# alan.net
KiCad netlist of a schematic drawn in EasyEDA Pro
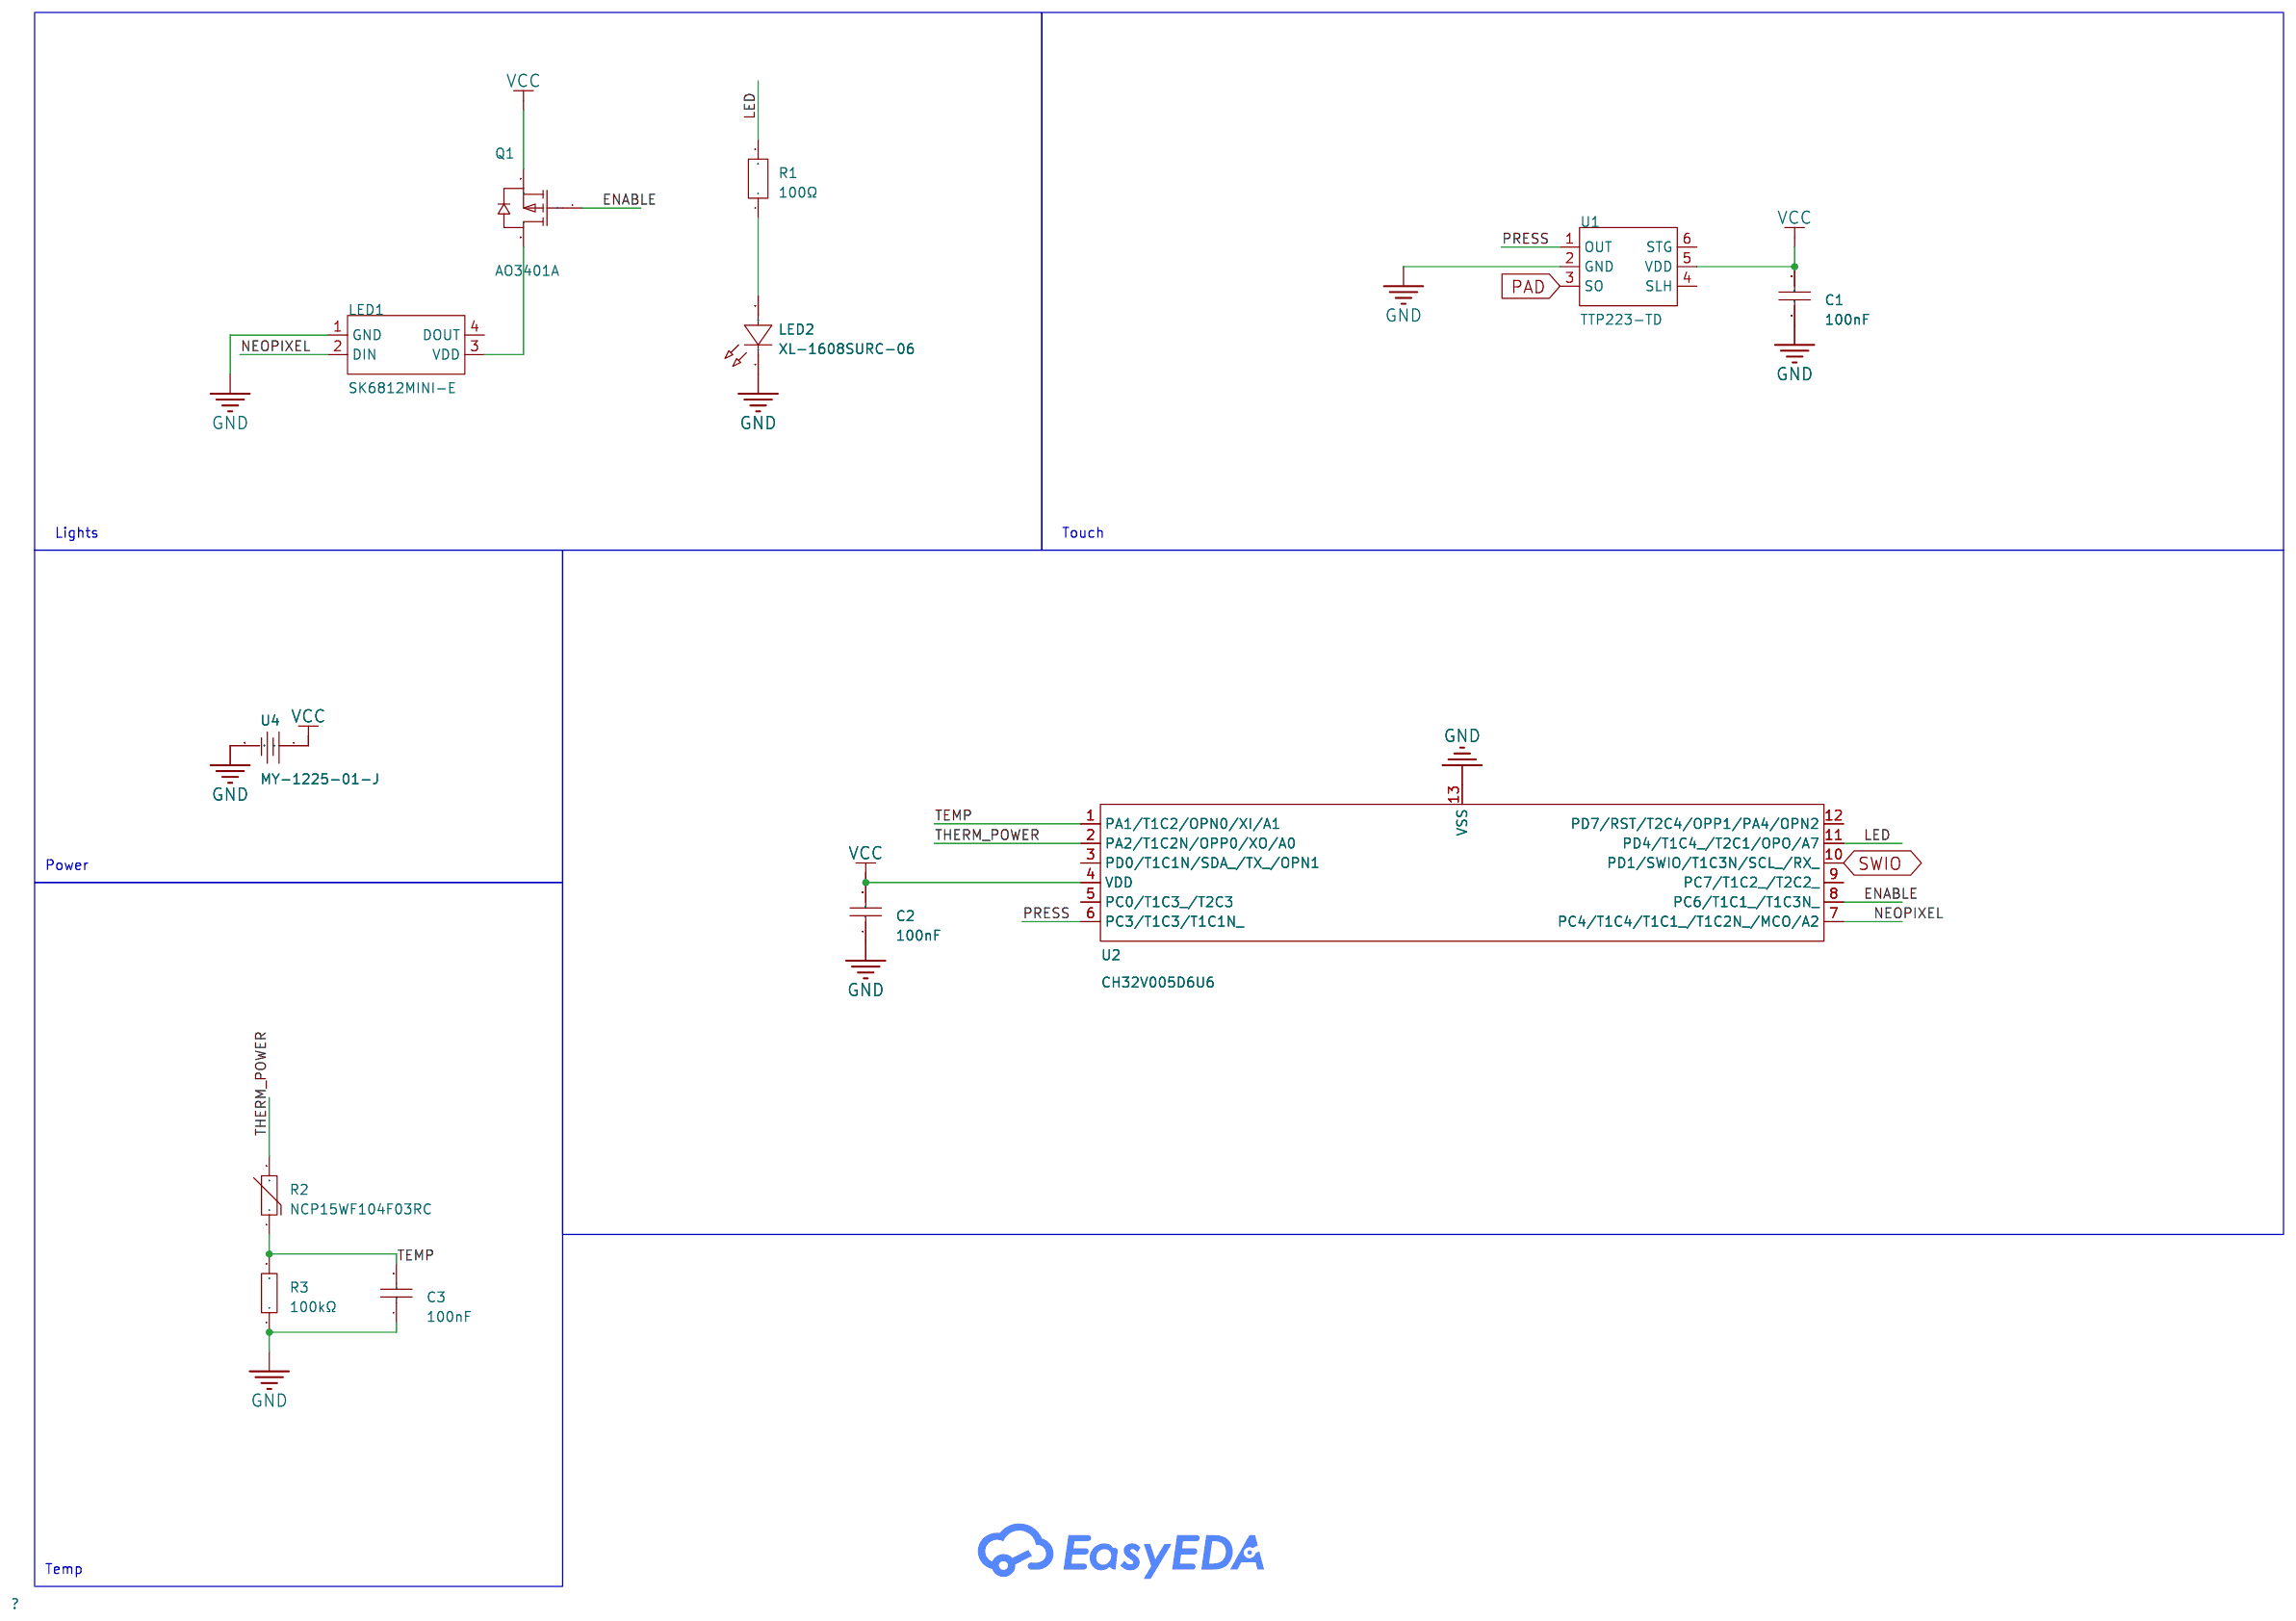
[diagram p0: schematic sheet]

(export (version "E")
  (design (tool "Eeschema 10.0.6"))
  (components
    (comp (ref "C1")
      (value "100nF")
      (footprint "easyedapro:C0402")
      (fields
        (field (name "Manufacturer Part") "CC0402KRX7R9BB104")
        (field (name "Manufacturer") "YAGEO(国巨)")
      )
      (libsource (lib "easyedapro") (part "CC0402KRX7R9BB104"))
    )
    (comp (ref "C2")
      (value "100nF")
      (footprint "easyedapro:C0402")
      (fields
        (field (name "Manufacturer Part") "CC0402KRX7R9BB104")
        (field (name "Manufacturer") "YAGEO(国巨)")
      )
      (libsource (lib "easyedapro") (part "CC0402KRX7R9BB104"))
    )
    (comp (ref "C3")
      (value "100nF")
      (footprint "easyedapro:C0402")
      (fields
        (field (name "Manufacturer Part") "CC0402KRX7R9BB104")
        (field (name "Manufacturer") "YAGEO(国巨)")
      )
      (libsource (lib "easyedapro") (part "CC0402KRX7R9BB104"))
    )
    (comp (ref "LED1")
      (value "SK6812MINI-E")
      (footprint "easyedapro:LED-SMD_4P-L3.2-W2.8-LS5.9_SK6812MINI-E")
      (fields (field (name "Manufacturer") "欧思科光电"))
      (libsource (lib "easyedapro") (part "SK6812MINI-E_C5149201"))
    )
    (comp (ref "LED2")
      (value "XL-1608SURC-06")
      (footprint "easyedapro:LED0603-RD_RED")
      (fields (field (name "Manufacturer") "XINGLIGHT(成兴光)"))
      (libsource (lib "easyedapro") (part "XL-1608SURC-06"))
    )
    (comp (ref "Q1")
      (value "AO3401A")
      (footprint "easyedapro:SOT-23_L2.9-W1.3-P1.90-LS2.4-BR")
      (fields (field (name "Manufacturer") "AOS"))
      (libsource (lib "easyedapro") (part "AO3401A"))
    )
    (comp (ref "R1")
      (value "100Ω")
      (footprint "easyedapro:R0402")
      (fields (field (name "Manufacturer Part") "ERJ2RKF1000X") (field (name "Manufacturer") "PANASONIC(松下)"))
      (libsource (lib "easyedapro") (part "ERJ2RKF1000X"))
    )
    (comp (ref "R2")
      (value "NCP15WF104F03RC")
      (footprint "easyedapro:R0402")
      (fields (field (name "Manufacturer") "muRata(村田)"))
      (libsource (lib "easyedapro") (part "NCP15WF104F03RC"))
    )
    (comp (ref "R3")
      (value "100kΩ")
      (footprint "easyedapro:R0402")
      (fields (field (name "Manufacturer Part") "RC0402FR-07100KL") (field (name "Manufacturer") "YAGEO(国巨)"))
      (libsource (lib "easyedapro") (part "RC0402FR-07100KL"))
    )
    (comp (ref "U1")
      (value "TTP223-TD")
      (footprint "easyedapro:SOT-23-6_L2.9-W1.6-P0.95-LS2.9-BL")
      (description "Number of Channels:1 Voltage - Supply:2V~5.5V Voltage - Supply:2V~5.5V Current - Supply:3.5uA")
      (fields (field (name "Manufacturer") "TDSEMIC(拓电半导体)"))
      (libsource (lib "easyedapro") (part "TTP223-TD"))
    )
    (comp (ref "U2")
      (value "CH32V005D6U6")
      (footprint "easyedapro:QFN-12_L2.0-W2.0-P0.40-TL-EP1.1-1")
      (fields (field (name "Manufacturer") "WCH(南京沁恒)"))
      (libsource (lib "easyedapro") (part "CH32V005D6U6"))
    )
    (comp (ref "U4")
      (value "MY-1225-01-J")
      (footprint "easyedapro:BAT-SMD_MY-1225-01-J")
      (fields (field (name "Manufacturer") "MYOUNG(美阳)"))
      (libsource (lib "easyedapro") (part "MY-1225-01-J"))
    )
  )
  (nets
    (net (code "1") (name "/ENABLE") (class "Default")
      (node (ref "Q1") (pin "1") (pinfunction "G_1") (pintype "unspecified"))
      (node (ref "U2") (pin "8") (pinfunction "PC6/T1C1_/T1C3N__8") (pintype "unspecified"))
    )
    (net (code "2") (name "/LED") (class "Default")
      (node (ref "R1") (pin "2") (pinfunction "2_2") (pintype "unspecified"))
      (node (ref "U2") (pin "11") (pinfunction "PD4/T1C4_/T2C1/OPO/A7_11") (pintype "unspecified"))
    )
    (net (code "3") (name "/NEOPIXEL") (class "Default")
      (node (ref "LED1") (pin "2") (pinfunction "DIN_2") (pintype "unspecified"))
      (node (ref "U2") (pin "7") (pinfunction "PC4/T1C4/T1C1_/T1C2N_/MCO/A2_7") (pintype "unspecified"))
    )
    (net (code "4") (name "/PRESS") (class "Default")
      (node (ref "U1") (pin "1") (pinfunction "OUT_1") (pintype "unspecified"))
      (node (ref "U2") (pin "6") (pinfunction "PC3/T1C3/T1C1N__6") (pintype "unspecified"))
    )
    (net (code "5") (name "/TEMP") (class "Default")
      (node (ref "C3") (pin "2") (pinfunction "2_2") (pintype "input"))
      (node (ref "R2") (pin "1") (pinfunction "1_1") (pintype "input"))
      (node (ref "R3") (pin "2") (pinfunction "2_2") (pintype "input"))
      (node (ref "U2") (pin "1") (pinfunction "PA1/T1C2/OPN0/XI/A1_1") (pintype "unspecified"))
    )
    (net (code "6") (name "/THERM_POWER") (class "Default")
      (node (ref "R2") (pin "2") (pinfunction "2_2") (pintype "input"))
      (node (ref "U2") (pin "2") (pinfunction "PA2/T1C2N/OPP0/XO/A0_2") (pintype "unspecified"))
    )
    (net (code "7") (name "GND") (class "Default")
      (node (ref "C1") (pin "1") (pinfunction "1_1") (pintype "input"))
      (node (ref "C2") (pin "1") (pinfunction "1_1") (pintype "input"))
      (node (ref "C3") (pin "1") (pinfunction "1_1") (pintype "input"))
      (node (ref "LED1") (pin "1") (pinfunction "GND_1") (pintype "unspecified"))
      (node (ref "LED2") (pin "1") (pinfunction "K_1") (pintype "unspecified"))
      (node (ref "R3") (pin "1") (pinfunction "1_1") (pintype "input"))
      (node (ref "U1") (pin "2") (pinfunction "GND_2") (pintype "unspecified"))
      (node (ref "U2") (pin "13") (pinfunction "VSS_13") (pintype "unspecified"))
      (node (ref "U4") (pin "2") (pinfunction "2_2") (pintype "input"))
    )
    (net (code "8") (name "Net-(LED1-VDD)") (class "Default")
      (node (ref "LED1") (pin "3") (pinfunction "VDD_3") (pintype "unspecified"))
      (node (ref "Q1") (pin "3") (pinfunction "D_3") (pintype "unspecified"))
    )
    (net (code "9") (name "Net-(LED2-A)") (class "Default")
      (node (ref "LED2") (pin "2") (pinfunction "A_2") (pintype "unspecified"))
      (node (ref "R1") (pin "1") (pinfunction "1_1") (pintype "unspecified"))
    )
    (net (code "10") (name "PAD") (class "Default")
      (node (ref "U1") (pin "3") (pinfunction "SO_3") (pintype "unspecified"))
    )
    (net (code "11") (name "SWIO") (class "Default")
      (node (ref "U2") (pin "10") (pinfunction "PD1/SWIO/T1C3N/SCL_/RX__10") (pintype "unspecified"))
    )
    (net (code "12") (name "VCC") (class "Default")
      (node (ref "C1") (pin "2") (pinfunction "2_2") (pintype "input"))
      (node (ref "C2") (pin "2") (pinfunction "2_2") (pintype "input"))
      (node (ref "Q1") (pin "2") (pinfunction "S_2") (pintype "unspecified"))
      (node (ref "U1") (pin "5") (pinfunction "VDD_5") (pintype "unspecified"))
      (node (ref "U2") (pin "4") (pinfunction "VDD_4") (pintype "unspecified"))
      (node (ref "U4") (pin "1") (pinfunction "1_1") (pintype "input"))
    )
    (net (code "13") (name "unconnected-(LED1-DOUT-Pad4)") (class "Default")
      (node (ref "LED1") (pin "4") (pinfunction "DOUT_4") (pintype "unspecified"))
    )
    (net (code "14") (name "unconnected-(U1-SLH-Pad4)") (class "Default")
      (node (ref "U1") (pin "4") (pinfunction "SLH_4") (pintype "unspecified"))
    )
    (net (code "15") (name "unconnected-(U1-STG-Pad6)") (class "Default")
      (node (ref "U1") (pin "6") (pinfunction "STG_6") (pintype "unspecified"))
    )
    (net (code "16") (name "unconnected-(U2-PC0{slash}T1C3_{slash}T2C3-Pad5)") (class "Default")
      (node (ref "U2") (pin "5") (pinfunction "PC0/T1C3_/T2C3_5") (pintype "unspecified"))
    )
    (net (code "17") (name "unconnected-(U2-PC7{slash}T1C2_{slash}T2C2_-Pad9)") (class "Default")
      (node (ref "U2") (pin "9") (pinfunction "PC7/T1C2_/T2C2__9") (pintype "unspecified"))
    )
    (net (code "18") (name "unconnected-(U2-PD0{slash}T1C1N{slash}SDA_{slash}TX_{slash}OPN1-Pad3)") (class "Default")
      (node (ref "U2") (pin "3") (pinfunction "PD0/T1C1N/SDA_/TX_/OPN1_3") (pintype "unspecified"))
    )
    (net (code "19") (name "unconnected-(U2-PD7{slash}RST{slash}T2C4{slash}OPP1{slash}PA4{slash}OPN2-Pad12)") (class "Default")
      (node (ref "U2") (pin "12") (pinfunction "PD7/RST/T2C4/OPP1/PA4/OPN2_12") (pintype "unspecified"))
    )
  )
)
